# hand_pcb.net
KiCad netlist of a schematic drawn in EAGLE
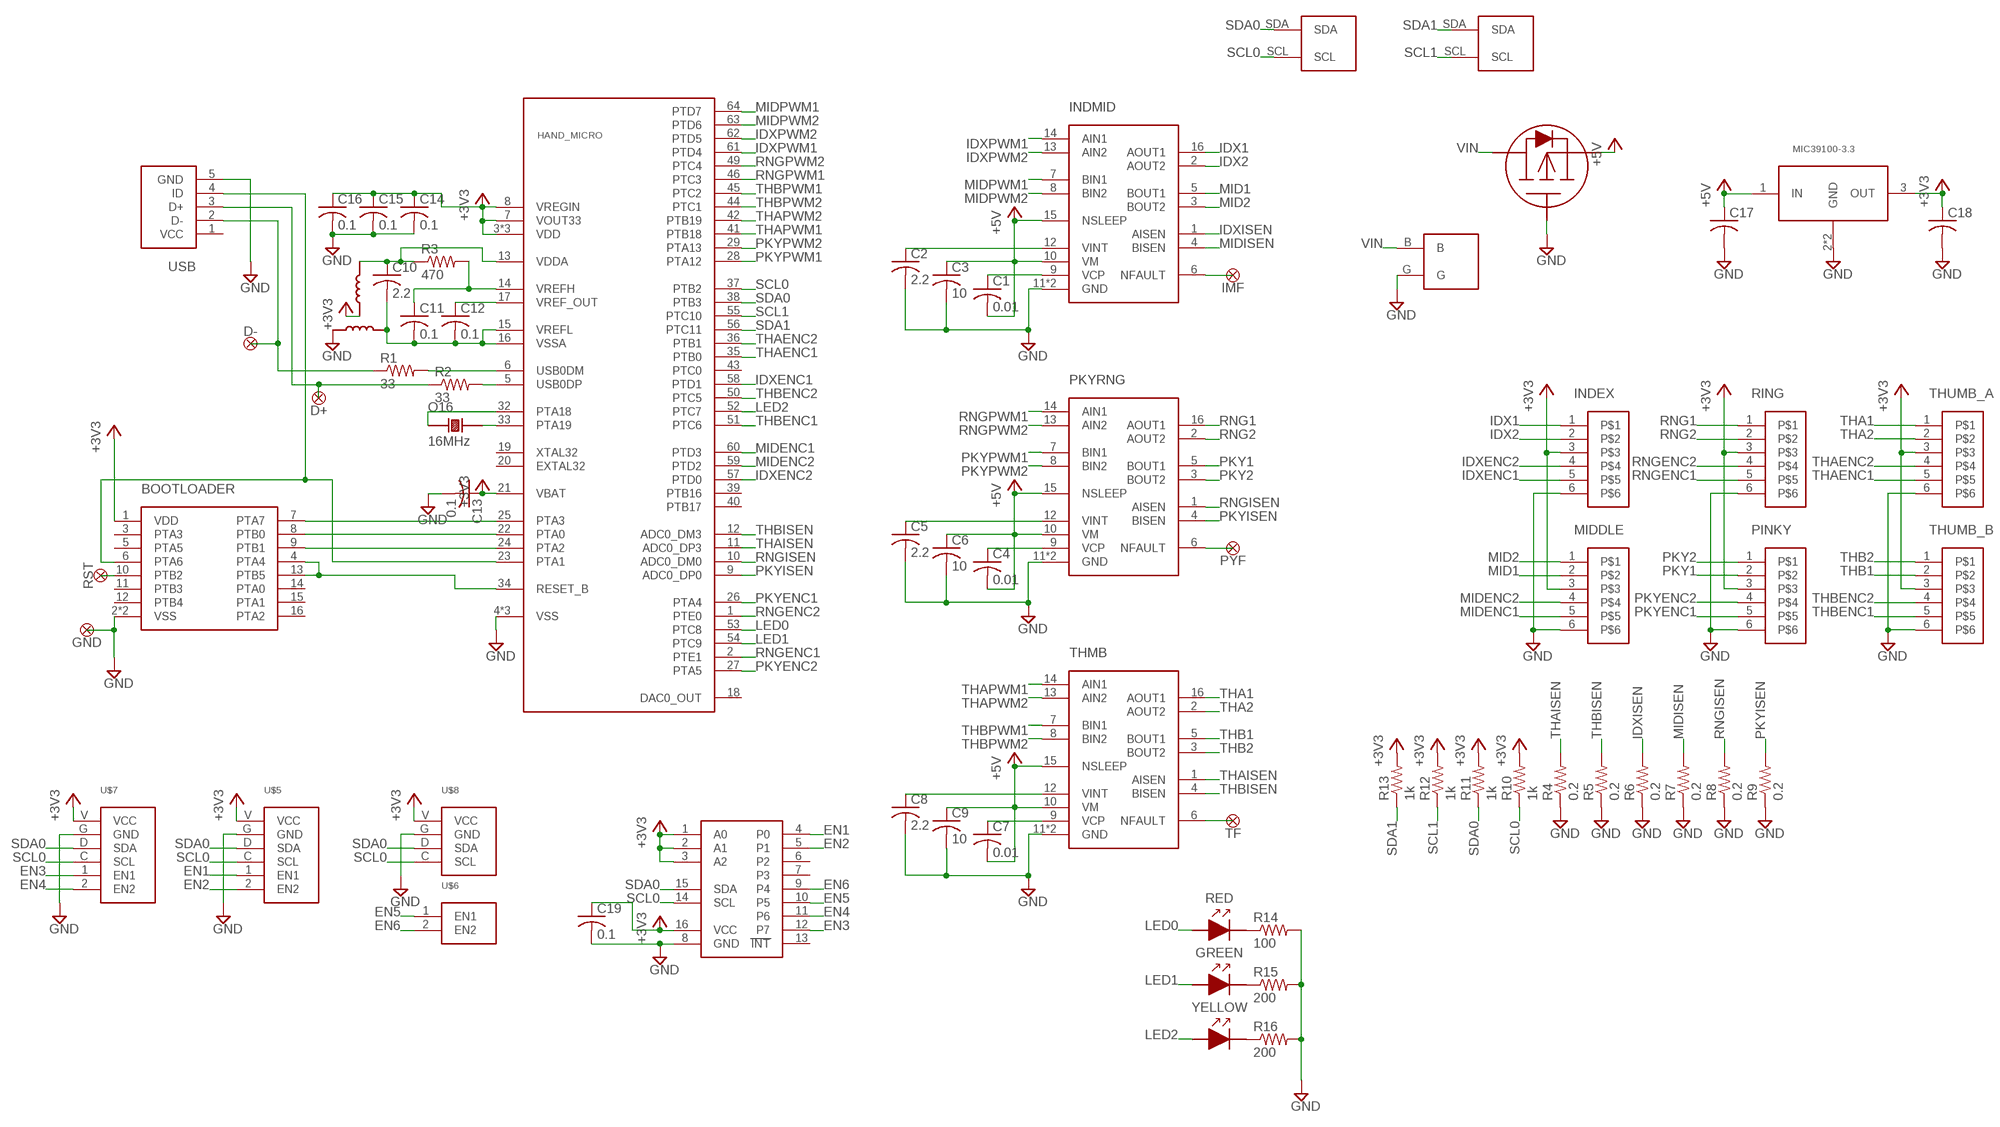
[diagram p0: schematic, sheet 1]

(export (version "E")
  (design (tool "Eeschema 10.0.6"))
  (components
    (comp (ref "BOOTLOADER")
      (value "MKL02Z32CORRECT")
      (footprint "eagle-import:QFN16")
      (libsource (lib "eagle-import") (part "MKL02Z32CORRECT"))
    )
    (comp (ref "C1")
      (value "0.01")
      (footprint "eagle-import:C0603")
      (libsource (lib "eagle-import") (part "C-USC0603"))
    )
    (comp (ref "C2")
      (value "2.2")
      (footprint "eagle-import:C0603")
      (libsource (lib "eagle-import") (part "C-USC0603"))
    )
    (comp (ref "C3")
      (value "10")
      (footprint "eagle-import:C0603")
      (libsource (lib "eagle-import") (part "C-USC0603"))
    )
    (comp (ref "C4")
      (value "0.01")
      (footprint "eagle-import:C0603")
      (libsource (lib "eagle-import") (part "C-USC0603"))
    )
    (comp (ref "C5")
      (value "2.2")
      (footprint "eagle-import:C0603")
      (libsource (lib "eagle-import") (part "C-USC0603"))
    )
    (comp (ref "C6")
      (value "10")
      (footprint "eagle-import:C0603")
      (libsource (lib "eagle-import") (part "C-USC0603"))
    )
    (comp (ref "C7")
      (value "0.01")
      (footprint "eagle-import:C0603")
      (libsource (lib "eagle-import") (part "C-USC0603"))
    )
    (comp (ref "C8")
      (value "2.2")
      (footprint "eagle-import:C0603")
      (libsource (lib "eagle-import") (part "C-USC0603"))
    )
    (comp (ref "C9")
      (value "10")
      (footprint "eagle-import:C0603")
      (libsource (lib "eagle-import") (part "C-USC0603"))
    )
    (comp (ref "C10")
      (value "2.2")
      (footprint "eagle-import:C0402")
      (libsource (lib "eagle-import") (part "C-USC0402"))
    )
    (comp (ref "C11")
      (value "0.1")
      (footprint "eagle-import:C0402")
      (libsource (lib "eagle-import") (part "C-USC0402"))
    )
    (comp (ref "C12")
      (value "0.1")
      (footprint "eagle-import:C0402")
      (libsource (lib "eagle-import") (part "C-USC0402"))
    )
    (comp (ref "C13")
      (value "0.1")
      (footprint "eagle-import:C0402")
      (libsource (lib "eagle-import") (part "C-USC0402"))
    )
    (comp (ref "C14")
      (value "0.1")
      (footprint "eagle-import:C0402")
      (libsource (lib "eagle-import") (part "C-USC0402"))
    )
    (comp (ref "C15")
      (value "0.1")
      (footprint "eagle-import:C0402")
      (libsource (lib "eagle-import") (part "C-USC0402"))
    )
    (comp (ref "C16")
      (value "0.1")
      (footprint "eagle-import:C0402")
      (libsource (lib "eagle-import") (part "C-USC0402"))
    )
    (comp (ref "C17")
      (value "C-USC0603")
      (footprint "eagle-import:C0603")
      (libsource (lib "eagle-import") (part "C-USC0603"))
    )
    (comp (ref "C18")
      (value "C-USC0603")
      (footprint "eagle-import:C0603")
      (libsource (lib "eagle-import") (part "C-USC0603"))
    )
    (comp (ref "C19")
      (value "0.1")
      (footprint "eagle-import:C0402")
      (libsource (lib "eagle-import") (part "C-USC0402"))
    )
    (comp (ref "D+")
      (value "TESTPAD")
      (footprint "eagle-import:TESTPAD")
      (libsource (lib "eagle-import") (part "TESTPAD"))
    )
    (comp (ref "D-")
      (value "TESTPAD")
      (footprint "eagle-import:TESTPAD")
      (libsource (lib "eagle-import") (part "TESTPAD"))
    )
    (comp (ref "GND")
      (value "TESTPAD")
      (footprint "eagle-import:TESTPAD")
      (libsource (lib "eagle-import") (part "TESTPAD"))
    )
    (comp (ref "GREEN")
      (value "LED0603")
      (footprint "eagle-import:L0603")
      (libsource (lib "eagle-import") (part "LED0603"))
    )
    (comp (ref "HAND_MICRO")
      (value "MK20DX256VLH7")
      (footprint "eagle-import:LQFP-64-10-10")
      (libsource (lib "eagle-import") (part "MK20DX256VLH7"))
    )
    (comp (ref "IMF")
      (value "TESTPAD")
      (footprint "eagle-import:TESTPAD")
      (libsource (lib "eagle-import") (part "TESTPAD"))
    )
    (comp (ref "INDEX")
      (value "DF57H-6PTOP")
      (footprint "eagle-import:DF57H-6P-TOP")
      (libsource (lib "eagle-import") (part "DF57H-6PTOP"))
    )
    (comp (ref "INDMID")
      (value "DRV8833")
      (footprint "eagle-import:WQFN-16")
      (libsource (lib "eagle-import") (part "DRV8833"))
    )
    (comp (ref "MIDDLE")
      (value "DF57H-6PTOP")
      (footprint "eagle-import:DF57H-6P-TOP")
      (libsource (lib "eagle-import") (part "DF57H-6PTOP"))
    )
    (comp (ref "O16")
      (value "16MHz")
      (footprint "eagle-import:NX3225SA")
      (libsource (lib "eagle-import") (part "NX3225SA"))
    )
    (comp (ref "PINKY")
      (value "DF57H-6PTOP")
      (footprint "eagle-import:DF57H-6P-TOP")
      (libsource (lib "eagle-import") (part "DF57H-6PTOP"))
    )
    (comp (ref "PKYRNG")
      (value "DRV8833")
      (footprint "eagle-import:WQFN-16")
      (libsource (lib "eagle-import") (part "DRV8833"))
    )
    (comp (ref "PYF")
      (value "TESTPAD")
      (footprint "eagle-import:TESTPAD")
      (libsource (lib "eagle-import") (part "TESTPAD"))
    )
    (comp (ref "R1")
      (value "33")
      (footprint "eagle-import:R0402")
      (libsource (lib "eagle-import") (part "R-US_R0402"))
    )
    (comp (ref "R2")
      (value "33")
      (footprint "eagle-import:R0402")
      (libsource (lib "eagle-import") (part "R-US_R0402"))
    )
    (comp (ref "R3")
      (value "470")
      (footprint "eagle-import:R0402")
      (libsource (lib "eagle-import") (part "R-US_R0402"))
    )
    (comp (ref "R4")
      (value "0.2")
      (footprint "eagle-import:R1206")
      (libsource (lib "eagle-import") (part "R-US_R1206"))
    )
    (comp (ref "R5")
      (value "0.2")
      (footprint "eagle-import:R1206")
      (libsource (lib "eagle-import") (part "R-US_R1206"))
    )
    (comp (ref "R6")
      (value "0.2")
      (footprint "eagle-import:R1206")
      (libsource (lib "eagle-import") (part "R-US_R1206"))
    )
    (comp (ref "R7")
      (value "0.2")
      (footprint "eagle-import:R1206")
      (libsource (lib "eagle-import") (part "R-US_R1206"))
    )
    (comp (ref "R8")
      (value "0.2")
      (footprint "eagle-import:R1206")
      (libsource (lib "eagle-import") (part "R-US_R1206"))
    )
    (comp (ref "R9")
      (value "0.2")
      (footprint "eagle-import:R1206")
      (libsource (lib "eagle-import") (part "R-US_R1206"))
    )
    (comp (ref "R10")
      (value "1k")
      (footprint "eagle-import:R0603")
      (libsource (lib "eagle-import") (part "R-US_R0603"))
    )
    (comp (ref "R11")
      (value "1k")
      (footprint "eagle-import:R0603")
      (libsource (lib "eagle-import") (part "R-US_R0603"))
    )
    (comp (ref "R12")
      (value "1k")
      (footprint "eagle-import:R0603")
      (libsource (lib "eagle-import") (part "R-US_R0603"))
    )
    (comp (ref "R13")
      (value "1k")
      (footprint "eagle-import:R0603")
      (libsource (lib "eagle-import") (part "R-US_R0603"))
    )
    (comp (ref "R14")
      (value "100")
      (footprint "eagle-import:R0603")
      (libsource (lib "eagle-import") (part "R-US_R0603"))
    )
    (comp (ref "R15")
      (value "200")
      (footprint "eagle-import:R0603")
      (libsource (lib "eagle-import") (part "R-US_R0603"))
    )
    (comp (ref "R16")
      (value "200")
      (footprint "eagle-import:R0603")
      (libsource (lib "eagle-import") (part "R-US_R0603"))
    )
    (comp (ref "RED")
      (value "LED0603")
      (footprint "eagle-import:L0603")
      (libsource (lib "eagle-import") (part "LED0603"))
    )
    (comp (ref "RING")
      (value "DF57H-6PTOP")
      (footprint "eagle-import:DF57H-6P-TOP")
      (libsource (lib "eagle-import") (part "DF57H-6PTOP"))
    )
    (comp (ref "RST")
      (value "TESTPAD")
      (footprint "eagle-import:TESTPAD")
      (libsource (lib "eagle-import") (part "TESTPAD"))
    )
    (comp (ref "TF")
      (value "TESTPAD")
      (footprint "eagle-import:TESTPAD")
      (libsource (lib "eagle-import") (part "TESTPAD"))
    )
    (comp (ref "THMB")
      (value "DRV8833")
      (footprint "eagle-import:WQFN-16")
      (libsource (lib "eagle-import") (part "DRV8833"))
    )
    (comp (ref "THUMB_A")
      (value "DF57H-6PTOP")
      (footprint "eagle-import:DF57H-6P-TOP")
      (libsource (lib "eagle-import") (part "DF57H-6PTOP"))
    )
    (comp (ref "THUMB_B")
      (value "DF57H-6PTOP")
      (footprint "eagle-import:DF57H-6P-TOP")
      (libsource (lib "eagle-import") (part "DF57H-6PTOP"))
    )
    (comp (ref "U$1")
      (value "TCA9534TSSOP")
      (footprint "eagle-import:TSSOP16")
      (libsource (lib "eagle-import") (part "TCA9534TSSOP"))
    )
    (comp (ref "U$2")
      (value "SPD15P10PLG")
      (footprint "eagle-import:PG-TO-252-3")
      (libsource (lib "eagle-import") (part "SPD15P10PLG"))
    )
    (comp (ref "U$3")
      (value "FERRITE600OHM100MHZ")
      (footprint "eagle-import:L0603")
      (libsource (lib "eagle-import") (part "FERRITE600OHM100MHZ"))
    )
    (comp (ref "U$4")
      (value "FERRITE600OHM100MHZ")
      (footprint "eagle-import:L0603")
      (libsource (lib "eagle-import") (part "FERRITE600OHM100MHZ"))
    )
    (comp (ref "U$5")
      (value "PSENSE")
      (footprint "eagle-import:PSENSE")
      (libsource (lib "eagle-import") (part "PSENSE"))
    )
    (comp (ref "U$6")
      (value "PSENSE2")
      (footprint "eagle-import:PSENSE2")
      (libsource (lib "eagle-import") (part "PSENSE2"))
    )
    (comp (ref "U$7")
      (value "PSENSE")
      (footprint "eagle-import:PSENSE")
      (libsource (lib "eagle-import") (part "PSENSE"))
    )
    (comp (ref "U$8")
      (value "PSENSE4")
      (footprint "eagle-import:PSENSE4")
      (libsource (lib "eagle-import") (part "PSENSE4"))
    )
    (comp (ref "U$9")
      (value "MIC391003.3")
      (footprint "eagle-import:MIC39100")
      (libsource (lib "eagle-import") (part "MIC391003.3"))
    )
    (comp (ref "U$10")
      (value "THRUHOLE2")
      (footprint "eagle-import:THRUHOLE2")
      (libsource (lib "eagle-import") (part "THRUHOLE2"))
    )
    (comp (ref "U$11")
      (value "THRUHOLEI2C")
      (footprint "eagle-import:THRUHOLEI2C")
      (libsource (lib "eagle-import") (part "THRUHOLEI2C"))
    )
    (comp (ref "U$12")
      (value "THRUHOLEI2C")
      (footprint "eagle-import:THRUHOLEI2C")
      (libsource (lib "eagle-import") (part "THRUHOLEI2C"))
    )
    (comp (ref "USB")
      (value "10118194-0001LF")
      (footprint "eagle-import:10118194-0001LF")
      (libsource (lib "eagle-import") (part "10118194-0001LF"))
    )
    (comp (ref "YELLOW")
      (value "LED0603")
      (footprint "eagle-import:L0603")
      (libsource (lib "eagle-import") (part "LED0603"))
    )
  )
  (nets
    (net (code "1") (name "+3V3") (class "Default")
      (node (ref "BOOTLOADER") (pin "1") (pinfunction "VDD_1") (pintype "bidirectional"))
      (node (ref "C13") (pin "1") (pinfunction "1_1") (pintype "passive"))
      (node (ref "C14") (pin "1") (pinfunction "1_1") (pintype "passive"))
      (node (ref "C15") (pin "1") (pinfunction "1_1") (pintype "passive"))
      (node (ref "C16") (pin "1") (pinfunction "1_1") (pintype "passive"))
      (node (ref "C18") (pin "1") (pinfunction "1_1") (pintype "passive"))
      (node (ref "C19") (pin "1") (pinfunction "1_1") (pintype "passive"))
      (node (ref "HAND_MICRO") (pin "21") (pinfunction "VBAT_21") (pintype "bidirectional"))
      (node (ref "HAND_MICRO") (pin "3") (pinfunction "VDD_3") (pintype "bidirectional"))
      (node (ref "HAND_MICRO") (pin "30") (pinfunction "VDD_30") (pintype "bidirectional"))
      (node (ref "HAND_MICRO") (pin "48") (pinfunction "VDD_48") (pintype "bidirectional"))
      (node (ref "HAND_MICRO") (pin "7") (pinfunction "VOUT33_7") (pintype "bidirectional"))
      (node (ref "HAND_MICRO") (pin "8") (pinfunction "VREGIN_8") (pintype "bidirectional"))
      (node (ref "INDEX") (pin "3") (pinfunction "P$3_3") (pintype "bidirectional"))
      (node (ref "MIDDLE") (pin "3") (pinfunction "P$3_3") (pintype "bidirectional"))
      (node (ref "PINKY") (pin "3") (pinfunction "P$3_3") (pintype "bidirectional"))
      (node (ref "R10") (pin "2") (pinfunction "2_2") (pintype "passive"))
      (node (ref "R11") (pin "2") (pinfunction "2_2") (pintype "passive"))
      (node (ref "R12") (pin "2") (pinfunction "2_2") (pintype "passive"))
      (node (ref "R13") (pin "2") (pinfunction "2_2") (pintype "passive"))
      (node (ref "RING") (pin "3") (pinfunction "P$3_3") (pintype "bidirectional"))
      (node (ref "THUMB_A") (pin "3") (pinfunction "P$3_3") (pintype "bidirectional"))
      (node (ref "THUMB_B") (pin "3") (pinfunction "P$3_3") (pintype "bidirectional"))
      (node (ref "U$1") (pin "1") (pinfunction "A0_1") (pintype "bidirectional"))
      (node (ref "U$1") (pin "16") (pinfunction "VCC_16") (pintype "bidirectional"))
      (node (ref "U$1") (pin "2") (pinfunction "A1_2") (pintype "bidirectional"))
      (node (ref "U$1") (pin "3") (pinfunction "A2_3") (pintype "bidirectional"))
      (node (ref "U$4") (pin "1") (pinfunction "P$1_1") (pintype "bidirectional"))
      (node (ref "U$5") (pin "V") (pinfunction "VCC_V") (pintype "bidirectional"))
      (node (ref "U$7") (pin "V") (pinfunction "VCC_V") (pintype "bidirectional"))
      (node (ref "U$8") (pin "V") (pinfunction "VCC_V") (pintype "bidirectional"))
      (node (ref "U$9") (pin "3") (pinfunction "OUT_3") (pintype "bidirectional"))
    )
    (net (code "2") (name "+5V") (class "Default")
      (node (ref "C1") (pin "2") (pinfunction "2_2") (pintype "passive"))
      (node (ref "C17") (pin "1") (pinfunction "1_1") (pintype "passive"))
      (node (ref "C3") (pin "1") (pinfunction "1_1") (pintype "passive"))
      (node (ref "C4") (pin "2") (pinfunction "2_2") (pintype "passive"))
      (node (ref "C6") (pin "1") (pinfunction "1_1") (pintype "passive"))
      (node (ref "C7") (pin "2") (pinfunction "2_2") (pintype "passive"))
      (node (ref "C9") (pin "1") (pinfunction "1_1") (pintype "passive"))
      (node (ref "INDMID") (pin "10") (pinfunction "VM_10") (pintype "bidirectional"))
      (node (ref "INDMID") (pin "15") (pinfunction "NSLEEP_15") (pintype "bidirectional"))
      (node (ref "PKYRNG") (pin "10") (pinfunction "VM_10") (pintype "bidirectional"))
      (node (ref "PKYRNG") (pin "15") (pinfunction "NSLEEP_15") (pintype "bidirectional"))
      (node (ref "THMB") (pin "10") (pinfunction "VM_10") (pintype "bidirectional"))
      (node (ref "THMB") (pin "15") (pinfunction "NSLEEP_15") (pintype "bidirectional"))
      (node (ref "U$2") (pin "3") (pinfunction "3_3") (pintype "bidirectional"))
      (node (ref "U$9") (pin "1") (pinfunction "IN_1") (pintype "bidirectional"))
    )
    (net (code "3") (name "/EN1") (class "Default")
      (node (ref "U$1") (pin "4") (pinfunction "P0_4") (pintype "bidirectional"))
      (node (ref "U$5") (pin "1") (pinfunction "EN1_1") (pintype "bidirectional"))
    )
    (net (code "4") (name "/EN2") (class "Default")
      (node (ref "U$1") (pin "5") (pinfunction "P1_5") (pintype "bidirectional"))
      (node (ref "U$5") (pin "2") (pinfunction "EN2_2") (pintype "bidirectional"))
    )
    (net (code "5") (name "/EN3") (class "Default")
      (node (ref "U$1") (pin "12") (pinfunction "P7_12") (pintype "bidirectional"))
      (node (ref "U$7") (pin "1") (pinfunction "EN1_1") (pintype "bidirectional"))
    )
    (net (code "6") (name "/EN4") (class "Default")
      (node (ref "U$1") (pin "11") (pinfunction "P6_11") (pintype "bidirectional"))
      (node (ref "U$7") (pin "2") (pinfunction "EN2_2") (pintype "bidirectional"))
    )
    (net (code "7") (name "/EN5") (class "Default")
      (node (ref "U$1") (pin "10") (pinfunction "P5_10") (pintype "bidirectional"))
      (node (ref "U$6") (pin "1") (pinfunction "EN1_1") (pintype "bidirectional"))
    )
    (net (code "8") (name "/EN6") (class "Default")
      (node (ref "U$1") (pin "9") (pinfunction "P4_9") (pintype "bidirectional"))
      (node (ref "U$6") (pin "2") (pinfunction "EN2_2") (pintype "bidirectional"))
    )
    (net (code "9") (name "/IDX1") (class "Default")
      (node (ref "INDEX") (pin "1") (pinfunction "P$1_1") (pintype "bidirectional"))
      (node (ref "INDMID") (pin "16") (pinfunction "AOUT1_16") (pintype "bidirectional"))
    )
    (net (code "10") (name "/IDX2") (class "Default")
      (node (ref "INDEX") (pin "2") (pinfunction "P$2_2") (pintype "bidirectional"))
      (node (ref "INDMID") (pin "2") (pinfunction "AOUT2_2") (pintype "bidirectional"))
    )
    (net (code "11") (name "/IDXENC1") (class "Default")
      (node (ref "HAND_MICRO") (pin "58") (pinfunction "PTD1_58") (pintype "bidirectional"))
      (node (ref "INDEX") (pin "5") (pinfunction "P$5_5") (pintype "bidirectional"))
    )
    (net (code "12") (name "/IDXENC2") (class "Default")
      (node (ref "HAND_MICRO") (pin "57") (pinfunction "PTD0_57") (pintype "bidirectional"))
      (node (ref "INDEX") (pin "4") (pinfunction "P$4_4") (pintype "bidirectional"))
    )
    (net (code "13") (name "/IDXISEN") (class "Default")
      (node (ref "INDMID") (pin "1") (pinfunction "AISEN_1") (pintype "bidirectional"))
      (node (ref "R6") (pin "2") (pinfunction "2_2") (pintype "passive"))
    )
    (net (code "14") (name "/IDXPWM1") (class "Default")
      (node (ref "HAND_MICRO") (pin "61") (pinfunction "PTD4_61") (pintype "bidirectional"))
      (node (ref "INDMID") (pin "14") (pinfunction "AIN1_14") (pintype "bidirectional"))
    )
    (net (code "15") (name "/IDXPWM2") (class "Default")
      (node (ref "HAND_MICRO") (pin "62") (pinfunction "PTD5_62") (pintype "bidirectional"))
      (node (ref "INDMID") (pin "13") (pinfunction "AIN2_13") (pintype "bidirectional"))
    )
    (net (code "16") (name "/LED0") (class "Default")
      (node (ref "HAND_MICRO") (pin "53") (pinfunction "PTC8_53") (pintype "bidirectional"))
      (node (ref "RED") (pin "1") (pinfunction "P$1_1") (pintype "bidirectional"))
    )
    (net (code "17") (name "/LED1") (class "Default")
      (node (ref "GREEN") (pin "1") (pinfunction "P$1_1") (pintype "bidirectional"))
      (node (ref "HAND_MICRO") (pin "54") (pinfunction "PTC9_54") (pintype "bidirectional"))
    )
    (net (code "18") (name "/LED2") (class "Default")
      (node (ref "HAND_MICRO") (pin "52") (pinfunction "PTC7_52") (pintype "bidirectional"))
      (node (ref "YELLOW") (pin "1") (pinfunction "P$1_1") (pintype "bidirectional"))
    )
    (net (code "19") (name "/MID1") (class "Default")
      (node (ref "INDMID") (pin "5") (pinfunction "BOUT1_5") (pintype "bidirectional"))
      (node (ref "MIDDLE") (pin "2") (pinfunction "P$2_2") (pintype "bidirectional"))
    )
    (net (code "20") (name "/MID2") (class "Default")
      (node (ref "INDMID") (pin "3") (pinfunction "BOUT2_3") (pintype "bidirectional"))
      (node (ref "MIDDLE") (pin "1") (pinfunction "P$1_1") (pintype "bidirectional"))
    )
    (net (code "21") (name "/MIDENC1") (class "Default")
      (node (ref "HAND_MICRO") (pin "60") (pinfunction "PTD3_60") (pintype "bidirectional"))
      (node (ref "MIDDLE") (pin "5") (pinfunction "P$5_5") (pintype "bidirectional"))
    )
    (net (code "22") (name "/MIDENC2") (class "Default")
      (node (ref "HAND_MICRO") (pin "59") (pinfunction "PTD2_59") (pintype "bidirectional"))
      (node (ref "MIDDLE") (pin "4") (pinfunction "P$4_4") (pintype "bidirectional"))
    )
    (net (code "23") (name "/MIDISEN") (class "Default")
      (node (ref "INDMID") (pin "4") (pinfunction "BISEN_4") (pintype "bidirectional"))
      (node (ref "R7") (pin "2") (pinfunction "2_2") (pintype "passive"))
    )
    (net (code "24") (name "/MIDPWM1") (class "Default")
      (node (ref "HAND_MICRO") (pin "64") (pinfunction "PTD7_64") (pintype "bidirectional"))
      (node (ref "INDMID") (pin "7") (pinfunction "BIN1_7") (pintype "bidirectional"))
    )
    (net (code "25") (name "/MIDPWM2") (class "Default")
      (node (ref "HAND_MICRO") (pin "63") (pinfunction "PTD6_63") (pintype "bidirectional"))
      (node (ref "INDMID") (pin "8") (pinfunction "BIN2_8") (pintype "bidirectional"))
    )
    (net (code "26") (name "/PKY1") (class "Default")
      (node (ref "PINKY") (pin "2") (pinfunction "P$2_2") (pintype "bidirectional"))
      (node (ref "PKYRNG") (pin "5") (pinfunction "BOUT1_5") (pintype "bidirectional"))
    )
    (net (code "27") (name "/PKY2") (class "Default")
      (node (ref "PINKY") (pin "1") (pinfunction "P$1_1") (pintype "bidirectional"))
      (node (ref "PKYRNG") (pin "3") (pinfunction "BOUT2_3") (pintype "bidirectional"))
    )
    (net (code "28") (name "/PKYENC1") (class "Default")
      (node (ref "HAND_MICRO") (pin "26") (pinfunction "PTA4_26") (pintype "bidirectional"))
      (node (ref "PINKY") (pin "5") (pinfunction "P$5_5") (pintype "bidirectional"))
    )
    (net (code "29") (name "/PKYENC2") (class "Default")
      (node (ref "HAND_MICRO") (pin "27") (pinfunction "PTA5_27") (pintype "bidirectional"))
      (node (ref "PINKY") (pin "4") (pinfunction "P$4_4") (pintype "bidirectional"))
    )
    (net (code "30") (name "/PKYISEN") (class "Default")
      (node (ref "HAND_MICRO") (pin "9") (pinfunction "ADC0_DP0_9") (pintype "bidirectional"))
      (node (ref "PKYRNG") (pin "4") (pinfunction "BISEN_4") (pintype "bidirectional"))
      (node (ref "R9") (pin "2") (pinfunction "2_2") (pintype "passive"))
    )
    (net (code "31") (name "/PKYPWM1") (class "Default")
      (node (ref "HAND_MICRO") (pin "28") (pinfunction "PTA12_28") (pintype "bidirectional"))
      (node (ref "PKYRNG") (pin "7") (pinfunction "BIN1_7") (pintype "bidirectional"))
    )
    (net (code "32") (name "/PKYPWM2") (class "Default")
      (node (ref "HAND_MICRO") (pin "29") (pinfunction "PTA13_29") (pintype "bidirectional"))
      (node (ref "PKYRNG") (pin "8") (pinfunction "BIN2_8") (pintype "bidirectional"))
    )
    (net (code "33") (name "/RNG1") (class "Default")
      (node (ref "PKYRNG") (pin "16") (pinfunction "AOUT1_16") (pintype "bidirectional"))
      (node (ref "RING") (pin "1") (pinfunction "P$1_1") (pintype "bidirectional"))
    )
    (net (code "34") (name "/RNG2") (class "Default")
      (node (ref "PKYRNG") (pin "2") (pinfunction "AOUT2_2") (pintype "bidirectional"))
      (node (ref "RING") (pin "2") (pinfunction "P$2_2") (pintype "bidirectional"))
    )
    (net (code "35") (name "/RNGENC1") (class "Default")
      (node (ref "HAND_MICRO") (pin "2") (pinfunction "PTE1_2") (pintype "bidirectional"))
      (node (ref "RING") (pin "5") (pinfunction "P$5_5") (pintype "bidirectional"))
    )
    (net (code "36") (name "/RNGENC2") (class "Default")
      (node (ref "HAND_MICRO") (pin "1") (pinfunction "PTE0_1") (pintype "bidirectional"))
      (node (ref "RING") (pin "4") (pinfunction "P$4_4") (pintype "bidirectional"))
    )
    (net (code "37") (name "/RNGISEN") (class "Default")
      (node (ref "HAND_MICRO") (pin "10") (pinfunction "ADC0_DM0_10") (pintype "bidirectional"))
      (node (ref "PKYRNG") (pin "1") (pinfunction "AISEN_1") (pintype "bidirectional"))
      (node (ref "R8") (pin "2") (pinfunction "2_2") (pintype "passive"))
    )
    (net (code "38") (name "/RNGPWM1") (class "Default")
      (node (ref "HAND_MICRO") (pin "46") (pinfunction "PTC3_46") (pintype "bidirectional"))
      (node (ref "PKYRNG") (pin "14") (pinfunction "AIN1_14") (pintype "bidirectional"))
    )
    (net (code "39") (name "/RNGPWM2") (class "Default")
      (node (ref "HAND_MICRO") (pin "49") (pinfunction "PTC4_49") (pintype "bidirectional"))
      (node (ref "PKYRNG") (pin "13") (pinfunction "AIN2_13") (pintype "bidirectional"))
    )
    (net (code "40") (name "/SCL0") (class "Default")
      (node (ref "HAND_MICRO") (pin "37") (pinfunction "PTB2_37") (pintype "bidirectional"))
      (node (ref "R10") (pin "1") (pinfunction "1_1") (pintype "passive"))
      (node (ref "U$1") (pin "14") (pinfunction "SCL_14") (pintype "bidirectional"))
      (node (ref "U$11") (pin "SCL") (pinfunction "SCL_SCL") (pintype "bidirectional"))
      (node (ref "U$5") (pin "C") (pinfunction "SCL_C") (pintype "bidirectional"))
      (node (ref "U$7") (pin "C") (pinfunction "SCL_C") (pintype "bidirectional"))
      (node (ref "U$8") (pin "C") (pinfunction "SCL_C") (pintype "bidirectional"))
    )
    (net (code "41") (name "/SCL1") (class "Default")
      (node (ref "HAND_MICRO") (pin "55") (pinfunction "PTC10_55") (pintype "bidirectional"))
      (node (ref "R12") (pin "1") (pinfunction "1_1") (pintype "passive"))
      (node (ref "U$12") (pin "SCL") (pinfunction "SCL_SCL") (pintype "bidirectional"))
    )
    (net (code "42") (name "/SDA0") (class "Default")
      (node (ref "HAND_MICRO") (pin "38") (pinfunction "PTB3_38") (pintype "bidirectional"))
      (node (ref "R11") (pin "1") (pinfunction "1_1") (pintype "passive"))
      (node (ref "U$1") (pin "15") (pinfunction "SDA_15") (pintype "bidirectional"))
      (node (ref "U$11") (pin "SDA") (pinfunction "SDA_SDA") (pintype "bidirectional"))
      (node (ref "U$5") (pin "D") (pinfunction "SDA_D") (pintype "bidirectional"))
      (node (ref "U$7") (pin "D") (pinfunction "SDA_D") (pintype "bidirectional"))
      (node (ref "U$8") (pin "D") (pinfunction "SDA_D") (pintype "bidirectional"))
    )
    (net (code "43") (name "/SDA1") (class "Default")
      (node (ref "HAND_MICRO") (pin "56") (pinfunction "PTC11_56") (pintype "bidirectional"))
      (node (ref "R13") (pin "1") (pinfunction "1_1") (pintype "passive"))
      (node (ref "U$12") (pin "SDA") (pinfunction "SDA_SDA") (pintype "bidirectional"))
    )
    (net (code "44") (name "/THA1") (class "Default")
      (node (ref "THMB") (pin "16") (pinfunction "AOUT1_16") (pintype "bidirectional"))
      (node (ref "THUMB_A") (pin "1") (pinfunction "P$1_1") (pintype "bidirectional"))
    )
    (net (code "45") (name "/THA2") (class "Default")
      (node (ref "THMB") (pin "2") (pinfunction "AOUT2_2") (pintype "bidirectional"))
      (node (ref "THUMB_A") (pin "2") (pinfunction "P$2_2") (pintype "bidirectional"))
    )
    (net (code "46") (name "/THAENC1") (class "Default")
      (node (ref "HAND_MICRO") (pin "35") (pinfunction "PTB0_35") (pintype "bidirectional"))
      (node (ref "THUMB_A") (pin "5") (pinfunction "P$5_5") (pintype "bidirectional"))
    )
    (net (code "47") (name "/THAENC2") (class "Default")
      (node (ref "HAND_MICRO") (pin "36") (pinfunction "PTB1_36") (pintype "bidirectional"))
      (node (ref "THUMB_A") (pin "4") (pinfunction "P$4_4") (pintype "bidirectional"))
    )
    (net (code "48") (name "/THAISEN") (class "Default")
      (node (ref "HAND_MICRO") (pin "11") (pinfunction "ADC0_DP3_11") (pintype "bidirectional"))
      (node (ref "R4") (pin "2") (pinfunction "2_2") (pintype "passive"))
      (node (ref "THMB") (pin "1") (pinfunction "AISEN_1") (pintype "bidirectional"))
    )
    (net (code "49") (name "/THAPWM1") (class "Default")
      (node (ref "HAND_MICRO") (pin "41") (pinfunction "PTB18_41") (pintype "bidirectional"))
      (node (ref "THMB") (pin "14") (pinfunction "AIN1_14") (pintype "bidirectional"))
    )
    (net (code "50") (name "/THAPWM2") (class "Default")
      (node (ref "HAND_MICRO") (pin "42") (pinfunction "PTB19_42") (pintype "bidirectional"))
      (node (ref "THMB") (pin "13") (pinfunction "AIN2_13") (pintype "bidirectional"))
    )
    (net (code "51") (name "/THB1") (class "Default")
      (node (ref "THMB") (pin "5") (pinfunction "BOUT1_5") (pintype "bidirectional"))
      (node (ref "THUMB_B") (pin "2") (pinfunction "P$2_2") (pintype "bidirectional"))
    )
    (net (code "52") (name "/THB2") (class "Default")
      (node (ref "THMB") (pin "3") (pinfunction "BOUT2_3") (pintype "bidirectional"))
      (node (ref "THUMB_B") (pin "1") (pinfunction "P$1_1") (pintype "bidirectional"))
    )
    (net (code "53") (name "/THBENC1") (class "Default")
      (node (ref "HAND_MICRO") (pin "51") (pinfunction "PTC6_51") (pintype "bidirectional"))
      (node (ref "THUMB_B") (pin "5") (pinfunction "P$5_5") (pintype "bidirectional"))
    )
    (net (code "54") (name "/THBENC2") (class "Default")
      (node (ref "HAND_MICRO") (pin "50") (pinfunction "PTC5_50") (pintype "bidirectional"))
      (node (ref "THUMB_B") (pin "4") (pinfunction "P$4_4") (pintype "bidirectional"))
    )
    (net (code "55") (name "/THBISEN") (class "Default")
      (node (ref "HAND_MICRO") (pin "12") (pinfunction "ADC0_DM3_12") (pintype "bidirectional"))
      (node (ref "R5") (pin "2") (pinfunction "2_2") (pintype "passive"))
      (node (ref "THMB") (pin "4") (pinfunction "BISEN_4") (pintype "bidirectional"))
    )
    (net (code "56") (name "/THBPWM1") (class "Default")
      (node (ref "HAND_MICRO") (pin "45") (pinfunction "PTC2_45") (pintype "bidirectional"))
      (node (ref "THMB") (pin "7") (pinfunction "BIN1_7") (pintype "bidirectional"))
    )
    (net (code "57") (name "/THBPWM2") (class "Default")
      (node (ref "HAND_MICRO") (pin "44") (pinfunction "PTC1_44") (pintype "bidirectional"))
      (node (ref "THMB") (pin "8") (pinfunction "BIN2_8") (pintype "bidirectional"))
    )
    (net (code "58") (name "/VIN") (class "Default")
      (node (ref "U$10") (pin "B") (pinfunction "B_B") (pintype "bidirectional"))
      (node (ref "U$2") (pin "2") (pinfunction "2_2") (pintype "bidirectional"))
    )
    (net (code "59") (name "GND") (class "Default")
      (node (ref "BOOTLOADER") (pin "2") (pinfunction "VSS_2") (pintype "bidirectional"))
      (node (ref "BOOTLOADER") (pin "TH") (pinfunction "VSS_TH") (pintype "bidirectional"))
      (node (ref "C13") (pin "2") (pinfunction "2_2") (pintype "passive"))
      (node (ref "C14") (pin "2") (pinfunction "2_2") (pintype "passive"))
      (node (ref "C15") (pin "2") (pinfunction "2_2") (pintype "passive"))
      (node (ref "C16") (pin "2") (pinfunction "2_2") (pintype "passive"))
      (node (ref "C17") (pin "2") (pinfunction "2_2") (pintype "passive"))
      (node (ref "C18") (pin "2") (pinfunction "2_2") (pintype "passive"))
      (node (ref "C19") (pin "2") (pinfunction "2_2") (pintype "passive"))
      (node (ref "C2") (pin "2") (pinfunction "2_2") (pintype "passive"))
      (node (ref "C3") (pin "2") (pinfunction "2_2") (pintype "passive"))
      (node (ref "C5") (pin "2") (pinfunction "2_2") (pintype "passive"))
      (node (ref "C6") (pin "2") (pinfunction "2_2") (pintype "passive"))
      (node (ref "C8") (pin "2") (pinfunction "2_2") (pintype "passive"))
      (node (ref "C9") (pin "2") (pinfunction "2_2") (pintype "passive"))
      (node (ref "GND") (pin "P$1") (pinfunction "P$1_P$1") (pintype "bidirectional"))
      (node (ref "HAND_MICRO") (pin "31") (pinfunction "VSS_31") (pintype "bidirectional"))
      (node (ref "HAND_MICRO") (pin "4") (pinfunction "VSS_4") (pintype "bidirectional"))
      (node (ref "HAND_MICRO") (pin "47") (pinfunction "VSS_47") (pintype "bidirectional"))
      (node (ref "INDEX") (pin "6") (pinfunction "P$6_6") (pintype "bidirectional"))
      (node (ref "INDMID") (pin "11") (pinfunction "GND_11") (pintype "bidirectional"))
      (node (ref "INDMID") (pin "PPAD") (pinfunction "GND_PPAD") (pintype "bidirectional"))
      (node (ref "MIDDLE") (pin "6") (pinfunction "P$6_6") (pintype "bidirectional"))
      (node (ref "PINKY") (pin "6") (pinfunction "P$6_6") (pintype "bidirectional"))
      (node (ref "PKYRNG") (pin "11") (pinfunction "GND_11") (pintype "bidirectional"))
      (node (ref "PKYRNG") (pin "PPAD") (pinfunction "GND_PPAD") (pintype "bidirectional"))
      (node (ref "R14") (pin "2") (pinfunction "2_2") (pintype "passive"))
      (node (ref "R15") (pin "2") (pinfunction "2_2") (pintype "passive"))
      (node (ref "R16") (pin "2") (pinfunction "2_2") (pintype "passive"))
      (node (ref "R4") (pin "1") (pinfunction "1_1") (pintype "passive"))
      (node (ref "R5") (pin "1") (pinfunction "1_1") (pintype "passive"))
      (node (ref "R6") (pin "1") (pinfunction "1_1") (pintype "passive"))
      (node (ref "R7") (pin "1") (pinfunction "1_1") (pintype "passive"))
      (node (ref "R8") (pin "1") (pinfunction "1_1") (pintype "passive"))
      (node (ref "R9") (pin "1") (pinfunction "1_1") (pintype "passive"))
      (node (ref "RING") (pin "6") (pinfunction "P$6_6") (pintype "bidirectional"))
      (node (ref "THMB") (pin "11") (pinfunction "GND_11") (pintype "bidirectional"))
      (node (ref "THMB") (pin "PPAD") (pinfunction "GND_PPAD") (pintype "bidirectional"))
      (node (ref "THUMB_A") (pin "6") (pinfunction "P$6_6") (pintype "bidirectional"))
      (node (ref "THUMB_B") (pin "6") (pinfunction "P$6_6") (pintype "bidirectional"))
      (node (ref "U$1") (pin "8") (pinfunction "GND_8") (pintype "bidirectional"))
      (node (ref "U$10") (pin "G") (pinfunction "G_G") (pintype "bidirectional"))
      (node (ref "U$2") (pin "1") (pinfunction "1_1") (pintype "bidirectional"))
      (node (ref "U$3") (pin "1") (pinfunction "P$1_1") (pintype "bidirectional"))
      (node (ref "U$5") (pin "G") (pinfunction "GND_G") (pintype "bidirectional"))
      (node (ref "U$7") (pin "G") (pinfunction "GND_G") (pintype "bidirectional"))
      (node (ref "U$8") (pin "G") (pinfunction "GND_G") (pintype "bidirectional"))
      (node (ref "U$9") (pin "2") (pinfunction "GND_2") (pintype "bidirectional"))
      (node (ref "U$9") (pin "TAB") (pinfunction "GND_TAB") (pintype "bidirectional"))
      (node (ref "USB") (pin "5") (pinfunction "GND_5") (pintype "bidirectional"))
    )
    (net (code "60") (name "Net-(BOOTLOADER-PTA4)") (class "Default")
      (node (ref "BOOTLOADER") (pin "13") (pinfunction "PTB5_13") (pintype "bidirectional"))
      (node (ref "BOOTLOADER") (pin "4") (pinfunction "PTA4_4") (pintype "bidirectional"))
      (node (ref "HAND_MICRO") (pin "34") (pinfunction "RESET_B_34") (pintype "bidirectional"))
    )
    (net (code "61") (name "Net-(BOOTLOADER-PTA6)") (class "Default")
      (node (ref "BOOTLOADER") (pin "6") (pinfunction "PTA6_6") (pintype "bidirectional"))
      (node (ref "HAND_MICRO") (pin "23") (pinfunction "PTA1_23") (pintype "bidirectional"))
      (node (ref "USB") (pin "4") (pinfunction "ID_4") (pintype "bidirectional"))
    )
    (net (code "62") (name "Net-(BOOTLOADER-PTA7)") (class "Default")
      (node (ref "BOOTLOADER") (pin "7") (pinfunction "PTA7_7") (pintype "bidirectional"))
      (node (ref "HAND_MICRO") (pin "25") (pinfunction "PTA3_25") (pintype "bidirectional"))
    )
    (net (code "63") (name "Net-(BOOTLOADER-PTB0)") (class "Default")
      (node (ref "BOOTLOADER") (pin "8") (pinfunction "PTB0_8") (pintype "bidirectional"))
      (node (ref "HAND_MICRO") (pin "22") (pinfunction "PTA0_22") (pintype "bidirectional"))
    )
    (net (code "64") (name "Net-(BOOTLOADER-PTB1)") (class "Default")
      (node (ref "BOOTLOADER") (pin "9") (pinfunction "PTB1_9") (pintype "bidirectional"))
      (node (ref "HAND_MICRO") (pin "24") (pinfunction "PTA2_24") (pintype "bidirectional"))
    )
    (net (code "65") (name "Net-(BOOTLOADER-PTB2)") (class "Default")
      (node (ref "BOOTLOADER") (pin "10") (pinfunction "PTB2_10") (pintype "bidirectional"))
      (node (ref "RST") (pin "P$1") (pinfunction "P$1_P$1") (pintype "bidirectional"))
    )
    (net (code "66") (name "Net-(GREEN-P$2)") (class "Default")
      (node (ref "GREEN") (pin "2") (pinfunction "P$2_2") (pintype "bidirectional"))
      (node (ref "R15") (pin "1") (pinfunction "1_1") (pintype "passive"))
    )
    (net (code "67") (name "Net-(HAND_MICRO-PTA18)") (class "Default")
      (node (ref "HAND_MICRO") (pin "32") (pinfunction "PTA18_32") (pintype "bidirectional"))
      (node (ref "O16") (pin "1") (pinfunction "P$1_1") (pintype "bidirectional"))
    )
    (net (code "68") (name "Net-(HAND_MICRO-PTA19)") (class "Default")
      (node (ref "HAND_MICRO") (pin "33") (pinfunction "PTA19_33") (pintype "bidirectional"))
      (node (ref "O16") (pin "3") (pinfunction "P$2_3") (pintype "bidirectional"))
    )
    (net (code "69") (name "Net-(HAND_MICRO-USB0DM)") (class "Default")
      (node (ref "HAND_MICRO") (pin "6") (pinfunction "USB0DM_6") (pintype "bidirectional"))
      (node (ref "R1") (pin "2") (pinfunction "2_2") (pintype "passive"))
    )
    (net (code "70") (name "Net-(HAND_MICRO-USB0DP)") (class "Default")
      (node (ref "HAND_MICRO") (pin "5") (pinfunction "USB0DP_5") (pintype "bidirectional"))
      (node (ref "R2") (pin "2") (pinfunction "2_2") (pintype "passive"))
    )
    (net (code "71") (name "Net-(HAND_MICRO-VDDA)") (class "Default")
      (node (ref "C10") (pin "1") (pinfunction "1_1") (pintype "passive"))
      (node (ref "HAND_MICRO") (pin "13") (pinfunction "VDDA_13") (pintype "bidirectional"))
      (node (ref "R3") (pin "1") (pinfunction "1_1") (pintype "passive"))
      (node (ref "U$4") (pin "2") (pinfunction "P$2_2") (pintype "bidirectional"))
    )
    (net (code "72") (name "Net-(HAND_MICRO-VREFH)") (class "Default")
      (node (ref "C11") (pin "1") (pinfunction "1_1") (pintype "passive"))
      (node (ref "HAND_MICRO") (pin "14") (pinfunction "VREFH_14") (pintype "bidirectional"))
      (node (ref "R3") (pin "2") (pinfunction "2_2") (pintype "passive"))
    )
    (net (code "73") (name "Net-(HAND_MICRO-VREFL)") (class "Default")
      (node (ref "C10") (pin "2") (pinfunction "2_2") (pintype "passive"))
      (node (ref "C11") (pin "2") (pinfunction "2_2") (pintype "passive"))
      (node (ref "C12") (pin "2") (pinfunction "2_2") (pintype "passive"))
      (node (ref "HAND_MICRO") (pin "15") (pinfunction "VREFL_15") (pintype "bidirectional"))
      (node (ref "HAND_MICRO") (pin "16") (pinfunction "VSSA_16") (pintype "bidirectional"))
      (node (ref "U$3") (pin "2") (pinfunction "P$2_2") (pintype "bidirectional"))
    )
    (net (code "74") (name "Net-(HAND_MICRO-VREF_OUT)") (class "Default")
      (node (ref "C12") (pin "1") (pinfunction "1_1") (pintype "passive"))
      (node (ref "HAND_MICRO") (pin "17") (pinfunction "VREF_OUT_17") (pintype "bidirectional"))
    )
    (net (code "75") (name "Net-(INDMID-NFAULT)") (class "Default")
      (node (ref "IMF") (pin "P$1") (pinfunction "P$1_P$1") (pintype "bidirectional"))
      (node (ref "INDMID") (pin "6") (pinfunction "NFAULT_6") (pintype "bidirectional"))
    )
    (net (code "76") (name "Net-(INDMID-VCP)") (class "Default")
      (node (ref "C1") (pin "1") (pinfunction "1_1") (pintype "passive"))
      (node (ref "INDMID") (pin "9") (pinfunction "VCP_9") (pintype "bidirectional"))
    )
    (net (code "77") (name "Net-(INDMID-VINT)") (class "Default")
      (node (ref "C2") (pin "1") (pinfunction "1_1") (pintype "passive"))
      (node (ref "INDMID") (pin "12") (pinfunction "VINT_12") (pintype "bidirectional"))
    )
    (net (code "78") (name "Net-(PKYRNG-NFAULT)") (class "Default")
      (node (ref "PKYRNG") (pin "6") (pinfunction "NFAULT_6") (pintype "bidirectional"))
      (node (ref "PYF") (pin "P$1") (pinfunction "P$1_P$1") (pintype "bidirectional"))
    )
    (net (code "79") (name "Net-(PKYRNG-VCP)") (class "Default")
      (node (ref "C4") (pin "1") (pinfunction "1_1") (pintype "passive"))
      (node (ref "PKYRNG") (pin "9") (pinfunction "VCP_9") (pintype "bidirectional"))
    )
    (net (code "80") (name "Net-(PKYRNG-VINT)") (class "Default")
      (node (ref "C5") (pin "1") (pinfunction "1_1") (pintype "passive"))
      (node (ref "PKYRNG") (pin "12") (pinfunction "VINT_12") (pintype "bidirectional"))
    )
    (net (code "81") (name "Net-(RED-P$2)") (class "Default")
      (node (ref "R14") (pin "1") (pinfunction "1_1") (pintype "passive"))
      (node (ref "RED") (pin "2") (pinfunction "P$2_2") (pintype "bidirectional"))
    )
    (net (code "82") (name "Net-(THMB-NFAULT)") (class "Default")
      (node (ref "TF") (pin "P$1") (pinfunction "P$1_P$1") (pintype "bidirectional"))
      (node (ref "THMB") (pin "6") (pinfunction "NFAULT_6") (pintype "bidirectional"))
    )
    (net (code "83") (name "Net-(THMB-VCP)") (class "Default")
      (node (ref "C7") (pin "1") (pinfunction "1_1") (pintype "passive"))
      (node (ref "THMB") (pin "9") (pinfunction "VCP_9") (pintype "bidirectional"))
    )
    (net (code "84") (name "Net-(THMB-VINT)") (class "Default")
      (node (ref "C8") (pin "1") (pinfunction "1_1") (pintype "passive"))
      (node (ref "THMB") (pin "12") (pinfunction "VINT_12") (pintype "bidirectional"))
    )
    (net (code "85") (name "Net-(USB-D+)") (class "Default")
      (node (ref "D+") (pin "P$1") (pinfunction "P$1_P$1") (pintype "bidirectional"))
      (node (ref "R2") (pin "1") (pinfunction "1_1") (pintype "passive"))
      (node (ref "USB") (pin "3") (pinfunction "D+_3") (pintype "bidirectional"))
    )
    (net (code "86") (name "Net-(USB-D-)") (class "Default")
      (node (ref "D-") (pin "P$1") (pinfunction "P$1_P$1") (pintype "bidirectional"))
      (node (ref "R1") (pin "1") (pinfunction "1_1") (pintype "passive"))
      (node (ref "USB") (pin "2") (pinfunction "D-_2") (pintype "bidirectional"))
    )
    (net (code "87") (name "Net-(YELLOW-P$2)") (class "Default")
      (node (ref "R16") (pin "1") (pinfunction "1_1") (pintype "passive"))
      (node (ref "YELLOW") (pin "2") (pinfunction "P$2_2") (pintype "bidirectional"))
    )
    (net (code "88") (name "unconnected-(BOOTLOADER-PTA0-Pad14)") (class "Default")
      (node (ref "BOOTLOADER") (pin "14") (pinfunction "PTA0_14") (pintype "bidirectional"))
    )
    (net (code "89") (name "unconnected-(BOOTLOADER-PTA1-Pad15)") (class "Default")
      (node (ref "BOOTLOADER") (pin "15") (pinfunction "PTA1_15") (pintype "bidirectional"))
    )
    (net (code "90") (name "unconnected-(BOOTLOADER-PTA2-Pad16)") (class "Default")
      (node (ref "BOOTLOADER") (pin "16") (pinfunction "PTA2_16") (pintype "bidirectional"))
    )
    (net (code "91") (name "unconnected-(BOOTLOADER-PTA3-Pad3)") (class "Default")
      (node (ref "BOOTLOADER") (pin "3") (pinfunction "PTA3_3") (pintype "bidirectional"))
    )
    (net (code "92") (name "unconnected-(BOOTLOADER-PTA5-Pad5)") (class "Default")
      (node (ref "BOOTLOADER") (pin "5") (pinfunction "PTA5_5") (pintype "bidirectional"))
    )
    (net (code "93") (name "unconnected-(BOOTLOADER-PTB3-Pad11)") (class "Default")
      (node (ref "BOOTLOADER") (pin "11") (pinfunction "PTB3_11") (pintype "bidirectional"))
    )
    (net (code "94") (name "unconnected-(BOOTLOADER-PTB4-Pad12)") (class "Default")
      (node (ref "BOOTLOADER") (pin "12") (pinfunction "PTB4_12") (pintype "bidirectional"))
    )
    (net (code "95") (name "unconnected-(HAND_MICRO-DAC0_OUT-Pad18)") (class "Default")
      (node (ref "HAND_MICRO") (pin "18") (pinfunction "DAC0_OUT_18") (pintype "bidirectional"))
    )
    (net (code "96") (name "unconnected-(HAND_MICRO-EXTAL32-Pad20)") (class "Default")
      (node (ref "HAND_MICRO") (pin "20") (pinfunction "EXTAL32_20") (pintype "bidirectional"))
    )
    (net (code "97") (name "unconnected-(HAND_MICRO-PTB16-Pad39)") (class "Default")
      (node (ref "HAND_MICRO") (pin "39") (pinfunction "PTB16_39") (pintype "bidirectional"))
    )
    (net (code "98") (name "unconnected-(HAND_MICRO-PTB17-Pad40)") (class "Default")
      (node (ref "HAND_MICRO") (pin "40") (pinfunction "PTB17_40") (pintype "bidirectional"))
    )
    (net (code "99") (name "unconnected-(HAND_MICRO-PTC0-Pad43)") (class "Default")
      (node (ref "HAND_MICRO") (pin "43") (pinfunction "PTC0_43") (pintype "bidirectional"))
    )
    (net (code "100") (name "unconnected-(HAND_MICRO-XTAL32-Pad19)") (class "Default")
      (node (ref "HAND_MICRO") (pin "19") (pinfunction "XTAL32_19") (pintype "bidirectional"))
    )
    (net (code "101") (name "unconnected-(U$1-INT-Pad13)") (class "Default")
      (node (ref "U$1") (pin "13") (pinfunction "INT_13") (pintype "bidirectional"))
    )
    (net (code "102") (name "unconnected-(U$1-P2-Pad6)") (class "Default")
      (node (ref "U$1") (pin "6") (pinfunction "P2_6") (pintype "bidirectional"))
    )
    (net (code "103") (name "unconnected-(U$1-P3-Pad7)") (class "Default")
      (node (ref "U$1") (pin "7") (pinfunction "P3_7") (pintype "bidirectional"))
    )
    (net (code "104") (name "unconnected-(USB-VCC-Pad1)") (class "Default")
      (node (ref "USB") (pin "1") (pinfunction "VCC_1") (pintype "bidirectional"))
    )
  )
)
